# multiple_frequency_divider_1_1.net
KiCad netlist of a schematic drawn in EAGLE
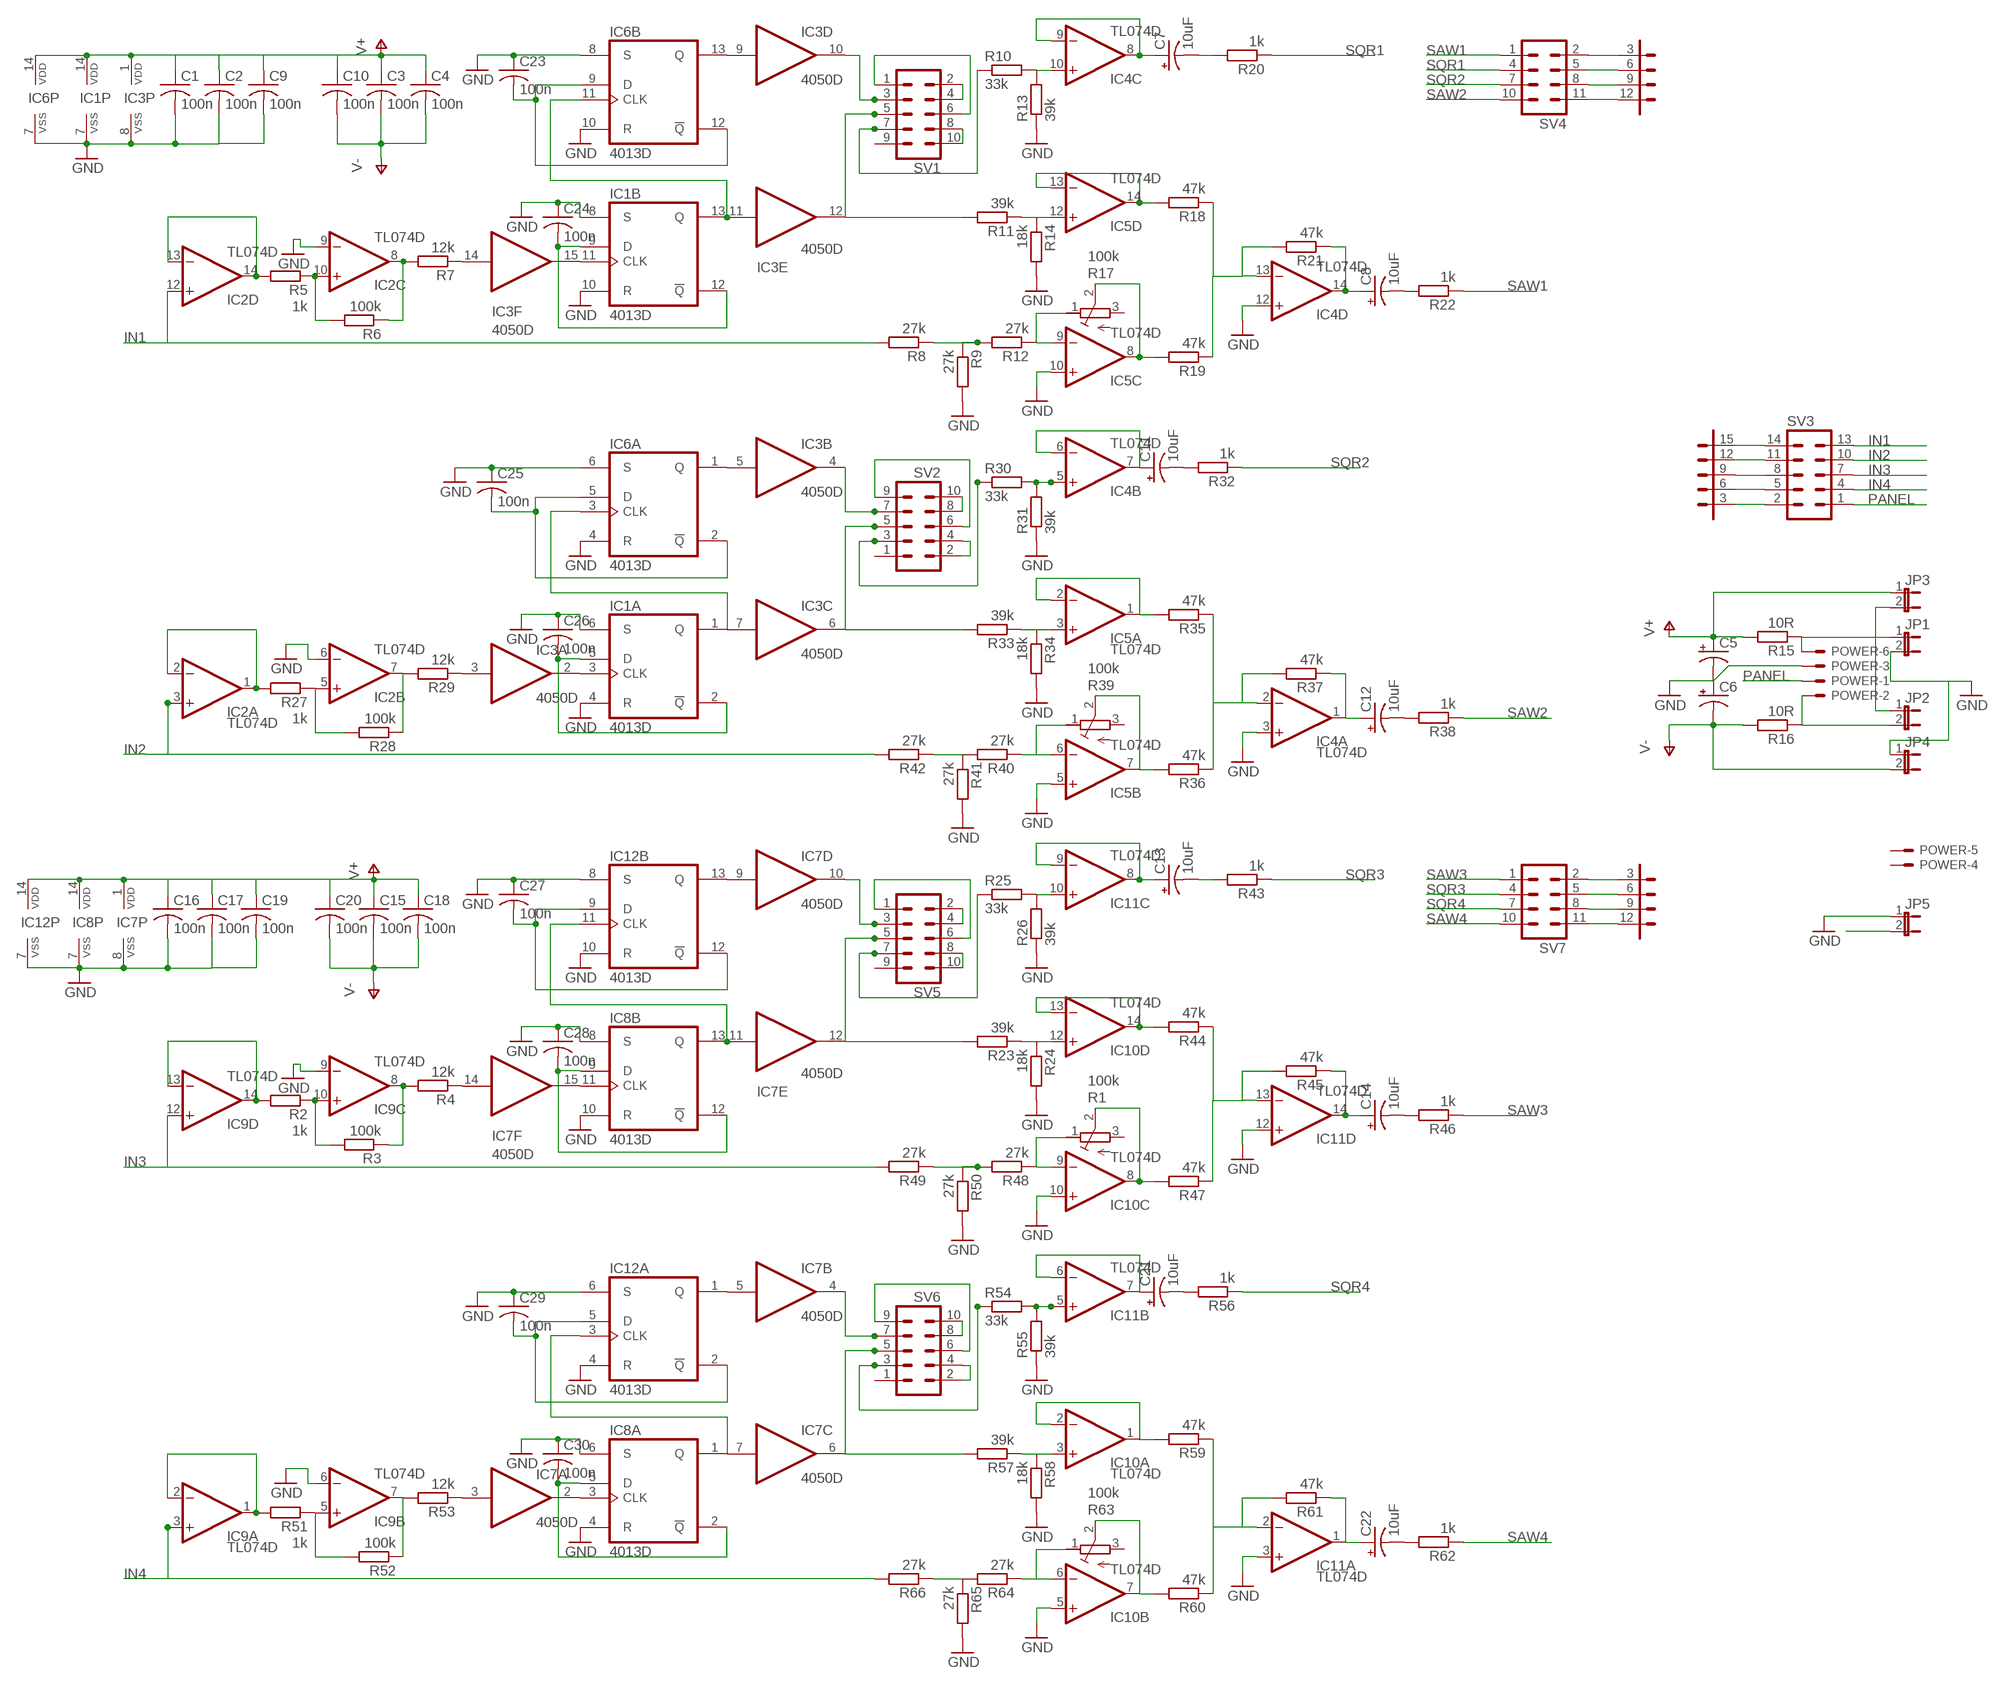
[diagram p0: schematic, sheet 1]

(export (version "E")
  (design (tool "Eeschema 10.0.6"))
  (components
    (comp (ref "C1")
      (value "100n")
      (footprint "eagle-import:C025-024X044")
      (libsource (lib "eagle-import") (part "C-US025-024X044"))
    )
    (comp (ref "C2")
      (value "100n")
      (footprint "eagle-import:C025-024X044")
      (libsource (lib "eagle-import") (part "C-US025-024X044"))
    )
    (comp (ref "C3")
      (value "100n")
      (footprint "eagle-import:C025-024X044")
      (libsource (lib "eagle-import") (part "C-US025-024X044"))
    )
    (comp (ref "C4")
      (value "100n")
      (footprint "eagle-import:C025-024X044")
      (libsource (lib "eagle-import") (part "C-US025-024X044"))
    )
    (comp (ref "C5")
      (value "CPOL-USE2.5-5")
      (footprint "eagle-import:E2,5-5")
      (libsource (lib "eagle-import") (part "CPOL-USE2.5-5"))
    )
    (comp (ref "C6")
      (value "CPOL-USE2.5-5")
      (footprint "eagle-import:E2,5-5")
      (libsource (lib "eagle-import") (part "CPOL-USE2.5-5"))
    )
    (comp (ref "C7")
      (value "10uF")
      (footprint "eagle-import:E2,5-5")
      (libsource (lib "eagle-import") (part "CPOL-USE2.5-5"))
    )
    (comp (ref "C8")
      (value "10uF")
      (footprint "eagle-import:E2,5-5")
      (libsource (lib "eagle-import") (part "CPOL-USE2.5-5"))
    )
    (comp (ref "C9")
      (value "100n")
      (footprint "eagle-import:C025-024X044")
      (libsource (lib "eagle-import") (part "C-US025-024X044"))
    )
    (comp (ref "C10")
      (value "100n")
      (footprint "eagle-import:C025-024X044")
      (libsource (lib "eagle-import") (part "C-US025-024X044"))
    )
    (comp (ref "C11")
      (value "10uF")
      (footprint "eagle-import:E2,5-5")
      (libsource (lib "eagle-import") (part "CPOL-USE2.5-5"))
    )
    (comp (ref "C12")
      (value "10uF")
      (footprint "eagle-import:E2,5-5")
      (libsource (lib "eagle-import") (part "CPOL-USE2.5-5"))
    )
    (comp (ref "C13")
      (value "10uF")
      (footprint "eagle-import:E2,5-5")
      (libsource (lib "eagle-import") (part "CPOL-USE2.5-5"))
    )
    (comp (ref "C14")
      (value "10uF")
      (footprint "eagle-import:E2,5-5")
      (libsource (lib "eagle-import") (part "CPOL-USE2.5-5"))
    )
    (comp (ref "C15")
      (value "100n")
      (footprint "eagle-import:C025-024X044")
      (libsource (lib "eagle-import") (part "C-US025-024X044"))
    )
    (comp (ref "C16")
      (value "100n")
      (footprint "eagle-import:C025-024X044")
      (libsource (lib "eagle-import") (part "C-US025-024X044"))
    )
    (comp (ref "C17")
      (value "100n")
      (footprint "eagle-import:C025-024X044")
      (libsource (lib "eagle-import") (part "C-US025-024X044"))
    )
    (comp (ref "C18")
      (value "100n")
      (footprint "eagle-import:C025-024X044")
      (libsource (lib "eagle-import") (part "C-US025-024X044"))
    )
    (comp (ref "C19")
      (value "100n")
      (footprint "eagle-import:C025-024X044")
      (libsource (lib "eagle-import") (part "C-US025-024X044"))
    )
    (comp (ref "C20")
      (value "100n")
      (footprint "eagle-import:C025-024X044")
      (libsource (lib "eagle-import") (part "C-US025-024X044"))
    )
    (comp (ref "C21")
      (value "10uF")
      (footprint "eagle-import:E2,5-5")
      (libsource (lib "eagle-import") (part "CPOL-USE2.5-5"))
    )
    (comp (ref "C22")
      (value "10uF")
      (footprint "eagle-import:E2,5-5")
      (libsource (lib "eagle-import") (part "CPOL-USE2.5-5"))
    )
    (comp (ref "C23")
      (value "100n")
      (footprint "eagle-import:C025-024X044")
      (libsource (lib "eagle-import") (part "C-US025-024X044"))
    )
    (comp (ref "C24")
      (value "100n")
      (footprint "eagle-import:C025-024X044")
      (libsource (lib "eagle-import") (part "C-US025-024X044"))
    )
    (comp (ref "C25")
      (value "100n")
      (footprint "eagle-import:C025-024X044")
      (libsource (lib "eagle-import") (part "C-US025-024X044"))
    )
    (comp (ref "C26")
      (value "100n")
      (footprint "eagle-import:C025-024X044")
      (libsource (lib "eagle-import") (part "C-US025-024X044"))
    )
    (comp (ref "C27")
      (value "100n")
      (footprint "eagle-import:C025-024X044")
      (libsource (lib "eagle-import") (part "C-US025-024X044"))
    )
    (comp (ref "C28")
      (value "100n")
      (footprint "eagle-import:C025-024X044")
      (libsource (lib "eagle-import") (part "C-US025-024X044"))
    )
    (comp (ref "C29")
      (value "100n")
      (footprint "eagle-import:C025-024X044")
      (libsource (lib "eagle-import") (part "C-US025-024X044"))
    )
    (comp (ref "C30")
      (value "100n")
      (footprint "eagle-import:C025-024X044")
      (libsource (lib "eagle-import") (part "C-US025-024X044"))
    )
    (comp (ref "IC1")
      (value "4013D")
      (footprint "eagle-import:SO14")
      (libsource (lib "eagle-import") (part "4013D"))
    )
    (comp (ref "IC2")
      (value "TL074D")
      (footprint "eagle-import:SO14")
      (libsource (lib "eagle-import") (part "TL074D"))
    )
    (comp (ref "IC3")
      (value "4050D")
      (footprint "eagle-import:SO16")
      (libsource (lib "eagle-import") (part "4050D"))
    )
    (comp (ref "IC4")
      (value "TL074D")
      (footprint "eagle-import:SO14")
      (libsource (lib "eagle-import") (part "TL074D"))
    )
    (comp (ref "IC5")
      (value "TL074D")
      (footprint "eagle-import:SO14")
      (libsource (lib "eagle-import") (part "TL074D"))
    )
    (comp (ref "IC6")
      (value "4013D")
      (footprint "eagle-import:SO14")
      (libsource (lib "eagle-import") (part "4013D"))
    )
    (comp (ref "IC7")
      (value "4050D")
      (footprint "eagle-import:SO16")
      (libsource (lib "eagle-import") (part "4050D"))
    )
    (comp (ref "IC8")
      (value "4013D")
      (footprint "eagle-import:SO14")
      (libsource (lib "eagle-import") (part "4013D"))
    )
    (comp (ref "IC9")
      (value "TL074D")
      (footprint "eagle-import:SO14")
      (libsource (lib "eagle-import") (part "TL074D"))
    )
    (comp (ref "IC10")
      (value "TL074D")
      (footprint "eagle-import:SO14")
      (libsource (lib "eagle-import") (part "TL074D"))
    )
    (comp (ref "IC11")
      (value "TL074D")
      (footprint "eagle-import:SO14")
      (libsource (lib "eagle-import") (part "TL074D"))
    )
    (comp (ref "IC12")
      (value "4013D")
      (footprint "eagle-import:SO14")
      (libsource (lib "eagle-import") (part "4013D"))
    )
    (comp (ref "JP1")
      (value "JP1E")
      (footprint "eagle-import:JP1")
      (libsource (lib "eagle-import") (part "JP1E"))
    )
    (comp (ref "JP2")
      (value "JP1E")
      (footprint "eagle-import:JP1")
      (libsource (lib "eagle-import") (part "JP1E"))
    )
    (comp (ref "JP3")
      (value "JP1E")
      (footprint "eagle-import:JP1")
      (libsource (lib "eagle-import") (part "JP1E"))
    )
    (comp (ref "JP4")
      (value "JP1E")
      (footprint "eagle-import:JP1")
      (libsource (lib "eagle-import") (part "JP1E"))
    )
    (comp (ref "JP5")
      (value "JP1E")
      (footprint "eagle-import:JP1")
      (libsource (lib "eagle-import") (part "JP1E"))
    )
    (comp (ref "POWER")
      (value "22-23-2061")
      (footprint "eagle-import:22-23-2061")
      (fields (field (name "MF") "MOLEX"))
      (libsource (lib "eagle-import") (part "22-23-2061"))
    )
    (comp (ref "R1")
      (value "100k")
      (footprint "eagle-import:RTRIMT93YA")
      (libsource (lib "eagle-import") (part "R-TRIMMT93YA"))
    )
    (comp (ref "R2")
      (value "1k")
      (footprint "eagle-import:0204_5")
      (libsource (lib "eagle-import") (part "R-EU_0204/5"))
    )
    (comp (ref "R3")
      (value "100k")
      (footprint "eagle-import:0204_5")
      (libsource (lib "eagle-import") (part "R-EU_0204/5"))
    )
    (comp (ref "R4")
      (value "12k")
      (footprint "eagle-import:0204_5")
      (libsource (lib "eagle-import") (part "R-EU_0204/5"))
    )
    (comp (ref "R5")
      (value "1k")
      (footprint "eagle-import:0204_5")
      (libsource (lib "eagle-import") (part "R-EU_0204/5"))
    )
    (comp (ref "R6")
      (value "100k")
      (footprint "eagle-import:0204_5")
      (libsource (lib "eagle-import") (part "R-EU_0204/5"))
    )
    (comp (ref "R7")
      (value "12k")
      (footprint "eagle-import:0204_5")
      (libsource (lib "eagle-import") (part "R-EU_0204/5"))
    )
    (comp (ref "R8")
      (value "27k")
      (footprint "eagle-import:0204_5")
      (libsource (lib "eagle-import") (part "R-EU_0204/5"))
    )
    (comp (ref "R9")
      (value "27k")
      (footprint "eagle-import:0204_5")
      (libsource (lib "eagle-import") (part "R-EU_0204/5"))
    )
    (comp (ref "R10")
      (value "33k")
      (footprint "eagle-import:0204_5")
      (libsource (lib "eagle-import") (part "R-EU_0204/5"))
    )
    (comp (ref "R11")
      (value "39k")
      (footprint "eagle-import:0204_5")
      (libsource (lib "eagle-import") (part "R-EU_0204/5"))
    )
    (comp (ref "R12")
      (value "27k")
      (footprint "eagle-import:0204_5")
      (libsource (lib "eagle-import") (part "R-EU_0204/5"))
    )
    (comp (ref "R13")
      (value "39k")
      (footprint "eagle-import:0204_5")
      (libsource (lib "eagle-import") (part "R-EU_0204/5"))
    )
    (comp (ref "R14")
      (value "18k")
      (footprint "eagle-import:0204_5")
      (libsource (lib "eagle-import") (part "R-EU_0204/5"))
    )
    (comp (ref "R15")
      (value "10R")
      (footprint "eagle-import:0207_7")
      (libsource (lib "eagle-import") (part "resistor_R-EU_0207/7"))
    )
    (comp (ref "R16")
      (value "10R")
      (footprint "eagle-import:0207_7")
      (libsource (lib "eagle-import") (part "resistor_R-EU_0207/7"))
    )
    (comp (ref "R17")
      (value "100k")
      (footprint "eagle-import:RTRIMT93YA")
      (libsource (lib "eagle-import") (part "R-TRIMMT93YA"))
    )
    (comp (ref "R18")
      (value "47k")
      (footprint "eagle-import:0204_5")
      (libsource (lib "eagle-import") (part "R-EU_0204/5"))
    )
    (comp (ref "R19")
      (value "47k")
      (footprint "eagle-import:0204_5")
      (libsource (lib "eagle-import") (part "R-EU_0204/5"))
    )
    (comp (ref "R20")
      (value "1k")
      (footprint "eagle-import:0204_5")
      (libsource (lib "eagle-import") (part "R-EU_0204/5"))
    )
    (comp (ref "R21")
      (value "47k")
      (footprint "eagle-import:0204_5")
      (libsource (lib "eagle-import") (part "R-EU_0204/5"))
    )
    (comp (ref "R22")
      (value "1k")
      (footprint "eagle-import:0204_5")
      (libsource (lib "eagle-import") (part "R-EU_0204/5"))
    )
    (comp (ref "R23")
      (value "39k")
      (footprint "eagle-import:0204_5")
      (libsource (lib "eagle-import") (part "R-EU_0204/5"))
    )
    (comp (ref "R24")
      (value "18k")
      (footprint "eagle-import:0204_5")
      (libsource (lib "eagle-import") (part "R-EU_0204/5"))
    )
    (comp (ref "R25")
      (value "33k")
      (footprint "eagle-import:0204_5")
      (libsource (lib "eagle-import") (part "R-EU_0204/5"))
    )
    (comp (ref "R26")
      (value "39k")
      (footprint "eagle-import:0204_5")
      (libsource (lib "eagle-import") (part "R-EU_0204/5"))
    )
    (comp (ref "R27")
      (value "1k")
      (footprint "eagle-import:0204_5")
      (libsource (lib "eagle-import") (part "R-EU_0204/5"))
    )
    (comp (ref "R28")
      (value "100k")
      (footprint "eagle-import:0204_5")
      (libsource (lib "eagle-import") (part "R-EU_0204/5"))
    )
    (comp (ref "R29")
      (value "12k")
      (footprint "eagle-import:0204_5")
      (libsource (lib "eagle-import") (part "R-EU_0204/5"))
    )
    (comp (ref "R30")
      (value "33k")
      (footprint "eagle-import:0204_5")
      (libsource (lib "eagle-import") (part "R-EU_0204/5"))
    )
    (comp (ref "R31")
      (value "39k")
      (footprint "eagle-import:0204_5")
      (libsource (lib "eagle-import") (part "R-EU_0204/5"))
    )
    (comp (ref "R32")
      (value "1k")
      (footprint "eagle-import:0204_5")
      (libsource (lib "eagle-import") (part "R-EU_0204/5"))
    )
    (comp (ref "R33")
      (value "39k")
      (footprint "eagle-import:0204_5")
      (libsource (lib "eagle-import") (part "R-EU_0204/5"))
    )
    (comp (ref "R34")
      (value "18k")
      (footprint "eagle-import:0204_5")
      (libsource (lib "eagle-import") (part "R-EU_0204/5"))
    )
    (comp (ref "R35")
      (value "47k")
      (footprint "eagle-import:0204_5")
      (libsource (lib "eagle-import") (part "R-EU_0204/5"))
    )
    (comp (ref "R36")
      (value "47k")
      (footprint "eagle-import:0204_5")
      (libsource (lib "eagle-import") (part "R-EU_0204/5"))
    )
    (comp (ref "R37")
      (value "47k")
      (footprint "eagle-import:0204_5")
      (libsource (lib "eagle-import") (part "R-EU_0204/5"))
    )
    (comp (ref "R38")
      (value "1k")
      (footprint "eagle-import:0204_5")
      (libsource (lib "eagle-import") (part "R-EU_0204/5"))
    )
    (comp (ref "R39")
      (value "100k")
      (footprint "eagle-import:RTRIMT93YA")
      (libsource (lib "eagle-import") (part "R-TRIMMT93YA"))
    )
    (comp (ref "R40")
      (value "27k")
      (footprint "eagle-import:0204_5")
      (libsource (lib "eagle-import") (part "R-EU_0204/5"))
    )
    (comp (ref "R41")
      (value "27k")
      (footprint "eagle-import:0204_5")
      (libsource (lib "eagle-import") (part "R-EU_0204/5"))
    )
    (comp (ref "R42")
      (value "27k")
      (footprint "eagle-import:0204_5")
      (libsource (lib "eagle-import") (part "R-EU_0204/5"))
    )
    (comp (ref "R43")
      (value "1k")
      (footprint "eagle-import:0204_5")
      (libsource (lib "eagle-import") (part "R-EU_0204/5"))
    )
    (comp (ref "R44")
      (value "47k")
      (footprint "eagle-import:0204_5")
      (libsource (lib "eagle-import") (part "R-EU_0204/5"))
    )
    (comp (ref "R45")
      (value "47k")
      (footprint "eagle-import:0204_5")
      (libsource (lib "eagle-import") (part "R-EU_0204/5"))
    )
    (comp (ref "R46")
      (value "1k")
      (footprint "eagle-import:0204_5")
      (libsource (lib "eagle-import") (part "R-EU_0204/5"))
    )
    (comp (ref "R47")
      (value "47k")
      (footprint "eagle-import:0204_5")
      (libsource (lib "eagle-import") (part "R-EU_0204/5"))
    )
    (comp (ref "R48")
      (value "27k")
      (footprint "eagle-import:0204_5")
      (libsource (lib "eagle-import") (part "R-EU_0204/5"))
    )
    (comp (ref "R49")
      (value "27k")
      (footprint "eagle-import:0204_5")
      (libsource (lib "eagle-import") (part "R-EU_0204/5"))
    )
    (comp (ref "R50")
      (value "27k")
      (footprint "eagle-import:0204_5")
      (libsource (lib "eagle-import") (part "R-EU_0204/5"))
    )
    (comp (ref "R51")
      (value "1k")
      (footprint "eagle-import:0204_5")
      (libsource (lib "eagle-import") (part "R-EU_0204/5"))
    )
    (comp (ref "R52")
      (value "100k")
      (footprint "eagle-import:0204_5")
      (libsource (lib "eagle-import") (part "R-EU_0204/5"))
    )
    (comp (ref "R53")
      (value "12k")
      (footprint "eagle-import:0204_5")
      (libsource (lib "eagle-import") (part "R-EU_0204/5"))
    )
    (comp (ref "R54")
      (value "33k")
      (footprint "eagle-import:0204_5")
      (libsource (lib "eagle-import") (part "R-EU_0204/5"))
    )
    (comp (ref "R55")
      (value "39k")
      (footprint "eagle-import:0204_5")
      (libsource (lib "eagle-import") (part "R-EU_0204/5"))
    )
    (comp (ref "R56")
      (value "1k")
      (footprint "eagle-import:0204_5")
      (libsource (lib "eagle-import") (part "R-EU_0204/5"))
    )
    (comp (ref "R57")
      (value "39k")
      (footprint "eagle-import:0204_5")
      (libsource (lib "eagle-import") (part "R-EU_0204/5"))
    )
    (comp (ref "R58")
      (value "18k")
      (footprint "eagle-import:0204_5")
      (libsource (lib "eagle-import") (part "R-EU_0204/5"))
    )
    (comp (ref "R59")
      (value "47k")
      (footprint "eagle-import:0204_5")
      (libsource (lib "eagle-import") (part "R-EU_0204/5"))
    )
    (comp (ref "R60")
      (value "47k")
      (footprint "eagle-import:0204_5")
      (libsource (lib "eagle-import") (part "R-EU_0204/5"))
    )
    (comp (ref "R61")
      (value "47k")
      (footprint "eagle-import:0204_5")
      (libsource (lib "eagle-import") (part "R-EU_0204/5"))
    )
    (comp (ref "R62")
      (value "1k")
      (footprint "eagle-import:0204_5")
      (libsource (lib "eagle-import") (part "R-EU_0204/5"))
    )
    (comp (ref "R63")
      (value "100k")
      (footprint "eagle-import:RTRIMT93YA")
      (libsource (lib "eagle-import") (part "R-TRIMMT93YA"))
    )
    (comp (ref "R64")
      (value "27k")
      (footprint "eagle-import:0204_5")
      (libsource (lib "eagle-import") (part "R-EU_0204/5"))
    )
    (comp (ref "R65")
      (value "27k")
      (footprint "eagle-import:0204_5")
      (libsource (lib "eagle-import") (part "R-EU_0204/5"))
    )
    (comp (ref "R66")
      (value "27k")
      (footprint "eagle-import:0204_5")
      (libsource (lib "eagle-import") (part "R-EU_0204/5"))
    )
    (comp (ref "SV1")
      (value "MA05-2")
      (footprint "eagle-import:MA05-2")
      (libsource (lib "eagle-import") (part "MA05-2"))
    )
    (comp (ref "SV2")
      (value "MA05-2")
      (footprint "eagle-import:MA05-2")
      (libsource (lib "eagle-import") (part "MA05-2"))
    )
    (comp (ref "SV3")
      (value "MA05-3")
      (footprint "eagle-import:MA05-3")
      (libsource (lib "eagle-import") (part "MA05-3"))
    )
    (comp (ref "SV4")
      (value "MA04-3")
      (footprint "eagle-import:MA04-3")
      (libsource (lib "eagle-import") (part "MA04-3"))
    )
    (comp (ref "SV5")
      (value "MA05-2")
      (footprint "eagle-import:MA05-2")
      (libsource (lib "eagle-import") (part "MA05-2"))
    )
    (comp (ref "SV6")
      (value "MA05-2")
      (footprint "eagle-import:MA05-2")
      (libsource (lib "eagle-import") (part "MA05-2"))
    )
    (comp (ref "SV7")
      (value "MA04-3")
      (footprint "eagle-import:MA04-3")
      (libsource (lib "eagle-import") (part "MA04-3"))
    )
  )
  (nets
    (net (code "1") (name "/IN1") (class "Default")
      (node (ref "IC2") (pin "12") (pinfunction "+IN_12") (pintype "input"))
      (node (ref "R8") (pin "2") (pinfunction "2_2") (pintype "passive"))
      (node (ref "SV3") (pin "13") (pinfunction "13_13") (pintype "passive"))
    )
    (net (code "2") (name "/IN2") (class "Default")
      (node (ref "IC2") (pin "3") (pinfunction "+IN_3") (pintype "input"))
      (node (ref "R42") (pin "2") (pinfunction "2_2") (pintype "passive"))
      (node (ref "SV3") (pin "10") (pinfunction "10_10") (pintype "passive"))
    )
    (net (code "3") (name "/IN3") (class "Default")
      (node (ref "IC9") (pin "12") (pinfunction "+IN_12") (pintype "input"))
      (node (ref "R49") (pin "2") (pinfunction "2_2") (pintype "passive"))
      (node (ref "SV3") (pin "7") (pinfunction "7_7") (pintype "passive"))
    )
    (net (code "4") (name "/IN4") (class "Default")
      (node (ref "IC9") (pin "3") (pinfunction "+IN_3") (pintype "input"))
      (node (ref "R66") (pin "2") (pinfunction "2_2") (pintype "passive"))
      (node (ref "SV3") (pin "4") (pinfunction "4_4") (pintype "passive"))
    )
    (net (code "5") (name "/PANEL") (class "Default")
      (node (ref "JP2") (pin "1") (pinfunction "1_1") (pintype "passive"))
      (node (ref "JP3") (pin "2") (pinfunction "2_2") (pintype "passive"))
      (node (ref "JP5") (pin "2") (pinfunction "2_2") (pintype "passive"))
      (node (ref "POWER") (pin "1") (pinfunction "S_1") (pintype "passive"))
      (node (ref "SV3") (pin "1") (pinfunction "1_1") (pintype "passive"))
    )
    (net (code "6") (name "/SAW1") (class "Default")
      (node (ref "R22") (pin "1") (pinfunction "1_1") (pintype "passive"))
      (node (ref "SV4") (pin "1") (pinfunction "1_1") (pintype "passive"))
    )
    (net (code "7") (name "/SAW2") (class "Default")
      (node (ref "R38") (pin "1") (pinfunction "1_1") (pintype "passive"))
      (node (ref "SV4") (pin "10") (pinfunction "10_10") (pintype "passive"))
    )
    (net (code "8") (name "/SAW3") (class "Default")
      (node (ref "R46") (pin "1") (pinfunction "1_1") (pintype "passive"))
      (node (ref "SV7") (pin "1") (pinfunction "1_1") (pintype "passive"))
    )
    (net (code "9") (name "/SAW4") (class "Default")
      (node (ref "R62") (pin "1") (pinfunction "1_1") (pintype "passive"))
      (node (ref "SV7") (pin "10") (pinfunction "10_10") (pintype "passive"))
    )
    (net (code "10") (name "/SQR1") (class "Default")
      (node (ref "R20") (pin "1") (pinfunction "1_1") (pintype "passive"))
      (node (ref "SV4") (pin "4") (pinfunction "4_4") (pintype "passive"))
    )
    (net (code "11") (name "/SQR2") (class "Default")
      (node (ref "R32") (pin "1") (pinfunction "1_1") (pintype "passive"))
      (node (ref "SV4") (pin "7") (pinfunction "7_7") (pintype "passive"))
    )
    (net (code "12") (name "/SQR3") (class "Default")
      (node (ref "R43") (pin "1") (pinfunction "1_1") (pintype "passive"))
      (node (ref "SV7") (pin "4") (pinfunction "4_4") (pintype "passive"))
    )
    (net (code "13") (name "/SQR4") (class "Default")
      (node (ref "R56") (pin "1") (pinfunction "1_1") (pintype "passive"))
      (node (ref "SV7") (pin "7") (pinfunction "7_7") (pintype "passive"))
    )
    (net (code "14") (name "GND") (class "Default")
      (node (ref "C1") (pin "2") (pinfunction "2_2") (pintype "passive"))
      (node (ref "C16") (pin "2") (pinfunction "2_2") (pintype "passive"))
      (node (ref "C17") (pin "2") (pinfunction "2_2") (pintype "passive"))
      (node (ref "C19") (pin "2") (pinfunction "2_2") (pintype "passive"))
      (node (ref "C2") (pin "2") (pinfunction "2_2") (pintype "passive"))
      (node (ref "C23") (pin "1") (pinfunction "1_1") (pintype "passive"))
      (node (ref "C24") (pin "1") (pinfunction "1_1") (pintype "passive"))
      (node (ref "C25") (pin "1") (pinfunction "1_1") (pintype "passive"))
      (node (ref "C26") (pin "1") (pinfunction "1_1") (pintype "passive"))
      (node (ref "C27") (pin "1") (pinfunction "1_1") (pintype "passive"))
      (node (ref "C28") (pin "1") (pinfunction "1_1") (pintype "passive"))
      (node (ref "C29") (pin "1") (pinfunction "1_1") (pintype "passive"))
      (node (ref "C30") (pin "1") (pinfunction "1_1") (pintype "passive"))
      (node (ref "C5") (pin "-") (pinfunction "-_-") (pintype "passive"))
      (node (ref "C6") (pin "+") (pinfunction "+_+") (pintype "passive"))
      (node (ref "C9") (pin "2") (pinfunction "2_2") (pintype "passive"))
      (node (ref "IC1") (pin "10") (pinfunction "R_10") (pintype "input"))
      (node (ref "IC1") (pin "4") (pinfunction "R_4") (pintype "input"))
      (node (ref "IC1") (pin "6") (pinfunction "S_6") (pintype "input"))
      (node (ref "IC1") (pin "7") (pinfunction "VSS_7") (pintype "power_in"))
      (node (ref "IC1") (pin "8") (pinfunction "S_8") (pintype "input"))
      (node (ref "IC10") (pin "10") (pinfunction "+IN_10") (pintype "input"))
      (node (ref "IC10") (pin "5") (pinfunction "+IN_5") (pintype "input"))
      (node (ref "IC11") (pin "12") (pinfunction "+IN_12") (pintype "input"))
      (node (ref "IC11") (pin "3") (pinfunction "+IN_3") (pintype "input"))
      (node (ref "IC12") (pin "10") (pinfunction "R_10") (pintype "input"))
      (node (ref "IC12") (pin "4") (pinfunction "R_4") (pintype "input"))
      (node (ref "IC12") (pin "6") (pinfunction "S_6") (pintype "input"))
      (node (ref "IC12") (pin "7") (pinfunction "VSS_7") (pintype "power_in"))
      (node (ref "IC12") (pin "8") (pinfunction "S_8") (pintype "input"))
      (node (ref "IC2") (pin "6") (pinfunction "-IN_6") (pintype "input"))
      (node (ref "IC2") (pin "9") (pinfunction "-IN_9") (pintype "input"))
      (node (ref "IC3") (pin "8") (pinfunction "VSS_8") (pintype "power_in"))
      (node (ref "IC4") (pin "12") (pinfunction "+IN_12") (pintype "input"))
      (node (ref "IC4") (pin "3") (pinfunction "+IN_3") (pintype "input"))
      (node (ref "IC5") (pin "10") (pinfunction "+IN_10") (pintype "input"))
      (node (ref "IC5") (pin "5") (pinfunction "+IN_5") (pintype "input"))
      (node (ref "IC6") (pin "10") (pinfunction "R_10") (pintype "input"))
      (node (ref "IC6") (pin "4") (pinfunction "R_4") (pintype "input"))
      (node (ref "IC6") (pin "6") (pinfunction "S_6") (pintype "input"))
      (node (ref "IC6") (pin "7") (pinfunction "VSS_7") (pintype "power_in"))
      (node (ref "IC6") (pin "8") (pinfunction "S_8") (pintype "input"))
      (node (ref "IC7") (pin "8") (pinfunction "VSS_8") (pintype "power_in"))
      (node (ref "IC8") (pin "10") (pinfunction "R_10") (pintype "input"))
      (node (ref "IC8") (pin "4") (pinfunction "R_4") (pintype "input"))
      (node (ref "IC8") (pin "6") (pinfunction "S_6") (pintype "input"))
      (node (ref "IC8") (pin "7") (pinfunction "VSS_7") (pintype "power_in"))
      (node (ref "IC8") (pin "8") (pinfunction "S_8") (pintype "input"))
      (node (ref "IC9") (pin "6") (pinfunction "-IN_6") (pintype "input"))
      (node (ref "IC9") (pin "9") (pinfunction "-IN_9") (pintype "input"))
      (node (ref "JP1") (pin "2") (pinfunction "2_2") (pintype "passive"))
      (node (ref "JP4") (pin "1") (pinfunction "1_1") (pintype "passive"))
      (node (ref "JP5") (pin "1") (pinfunction "1_1") (pintype "passive"))
      (node (ref "POWER") (pin "3") (pinfunction "S_3") (pintype "passive"))
      (node (ref "R13") (pin "1") (pinfunction "1_1") (pintype "passive"))
      (node (ref "R14") (pin "2") (pinfunction "2_2") (pintype "passive"))
      (node (ref "R24") (pin "2") (pinfunction "2_2") (pintype "passive"))
      (node (ref "R26") (pin "1") (pinfunction "1_1") (pintype "passive"))
      (node (ref "R31") (pin "1") (pinfunction "1_1") (pintype "passive"))
      (node (ref "R34") (pin "2") (pinfunction "2_2") (pintype "passive"))
      (node (ref "R41") (pin "2") (pinfunction "2_2") (pintype "passive"))
      (node (ref "R50") (pin "2") (pinfunction "2_2") (pintype "passive"))
      (node (ref "R55") (pin "1") (pinfunction "1_1") (pintype "passive"))
      (node (ref "R58") (pin "2") (pinfunction "2_2") (pintype "passive"))
      (node (ref "R65") (pin "2") (pinfunction "2_2") (pintype "passive"))
      (node (ref "R9") (pin "2") (pinfunction "2_2") (pintype "passive"))
    )
    (net (code "15") (name "Net-(C7-Pad-)") (class "Default")
      (node (ref "C7") (pin "-") (pinfunction "-_-") (pintype "passive"))
      (node (ref "R20") (pin "2") (pinfunction "2_2") (pintype "passive"))
    )
    (net (code "16") (name "Net-(C8-Pad-)") (class "Default")
      (node (ref "C8") (pin "-") (pinfunction "-_-") (pintype "passive"))
      (node (ref "R22") (pin "2") (pinfunction "2_2") (pintype "passive"))
    )
    (net (code "17") (name "Net-(C11-Pad-)") (class "Default")
      (node (ref "C11") (pin "-") (pinfunction "-_-") (pintype "passive"))
      (node (ref "R32") (pin "2") (pinfunction "2_2") (pintype "passive"))
    )
    (net (code "18") (name "Net-(C12-Pad-)") (class "Default")
      (node (ref "C12") (pin "-") (pinfunction "-_-") (pintype "passive"))
      (node (ref "R38") (pin "2") (pinfunction "2_2") (pintype "passive"))
    )
    (net (code "19") (name "Net-(C13-Pad-)") (class "Default")
      (node (ref "C13") (pin "-") (pinfunction "-_-") (pintype "passive"))
      (node (ref "R43") (pin "2") (pinfunction "2_2") (pintype "passive"))
    )
    (net (code "20") (name "Net-(C14-Pad-)") (class "Default")
      (node (ref "C14") (pin "-") (pinfunction "-_-") (pintype "passive"))
      (node (ref "R46") (pin "2") (pinfunction "2_2") (pintype "passive"))
    )
    (net (code "21") (name "Net-(C21-Pad-)") (class "Default")
      (node (ref "C21") (pin "-") (pinfunction "-_-") (pintype "passive"))
      (node (ref "R56") (pin "2") (pinfunction "2_2") (pintype "passive"))
    )
    (net (code "22") (name "Net-(C22-Pad-)") (class "Default")
      (node (ref "C22") (pin "-") (pinfunction "-_-") (pintype "passive"))
      (node (ref "R62") (pin "2") (pinfunction "2_2") (pintype "passive"))
    )
    (net (code "23") (name "Net-(IC1A-CLK)") (class "Default")
      (node (ref "IC1") (pin "3") (pinfunction "CLK_3") (pintype "input"))
      (node (ref "IC3") (pin "2") (pinfunction "O_2") (pintype "output"))
    )
    (net (code "24") (name "Net-(IC1A-D)") (class "Default")
      (node (ref "C26") (pin "2") (pinfunction "2_2") (pintype "passive"))
      (node (ref "IC1") (pin "2") (pinfunction "~{Q}_2") (pintype "output"))
      (node (ref "IC1") (pin "5") (pinfunction "D_5") (pintype "input"))
    )
    (net (code "25") (name "Net-(IC1A-Q)") (class "Default")
      (node (ref "IC1") (pin "1") (pinfunction "Q_1") (pintype "output"))
      (node (ref "IC3") (pin "7") (pinfunction "I_7") (pintype "input"))
      (node (ref "IC6") (pin "3") (pinfunction "CLK_3") (pintype "input"))
    )
    (net (code "26") (name "Net-(IC1B-CLK)") (class "Default")
      (node (ref "IC1") (pin "11") (pinfunction "CLK_11") (pintype "input"))
      (node (ref "IC3") (pin "15") (pinfunction "O_15") (pintype "output"))
    )
    (net (code "27") (name "Net-(IC1B-D)") (class "Default")
      (node (ref "C24") (pin "2") (pinfunction "2_2") (pintype "passive"))
      (node (ref "IC1") (pin "12") (pinfunction "~{Q}_12") (pintype "output"))
      (node (ref "IC1") (pin "9") (pinfunction "D_9") (pintype "input"))
    )
    (net (code "28") (name "Net-(IC1B-Q)") (class "Default")
      (node (ref "IC1") (pin "13") (pinfunction "Q_13") (pintype "output"))
      (node (ref "IC3") (pin "11") (pinfunction "I_11") (pintype "input"))
      (node (ref "IC6") (pin "11") (pinfunction "CLK_11") (pintype "input"))
    )
    (net (code "29") (name "Net-(IC2A--IN)") (class "Default")
      (node (ref "IC2") (pin "1") (pinfunction "OUT_1") (pintype "output"))
      (node (ref "IC2") (pin "2") (pinfunction "-IN_2") (pintype "input"))
      (node (ref "R27") (pin "2") (pinfunction "2_2") (pintype "passive"))
    )
    (net (code "30") (name "Net-(IC2B-+IN)") (class "Default")
      (node (ref "IC2") (pin "5") (pinfunction "+IN_5") (pintype "input"))
      (node (ref "R27") (pin "1") (pinfunction "1_1") (pintype "passive"))
      (node (ref "R28") (pin "2") (pinfunction "2_2") (pintype "passive"))
    )
    (net (code "31") (name "Net-(IC2B-OUT)") (class "Default")
      (node (ref "IC2") (pin "7") (pinfunction "OUT_7") (pintype "output"))
      (node (ref "R28") (pin "1") (pinfunction "1_1") (pintype "passive"))
      (node (ref "R29") (pin "2") (pinfunction "2_2") (pintype "passive"))
    )
    (net (code "32") (name "Net-(IC2C-+IN)") (class "Default")
      (node (ref "IC2") (pin "10") (pinfunction "+IN_10") (pintype "input"))
      (node (ref "R5") (pin "1") (pinfunction "1_1") (pintype "passive"))
      (node (ref "R6") (pin "2") (pinfunction "2_2") (pintype "passive"))
    )
    (net (code "33") (name "Net-(IC2C-OUT)") (class "Default")
      (node (ref "IC2") (pin "8") (pinfunction "OUT_8") (pintype "output"))
      (node (ref "R6") (pin "1") (pinfunction "1_1") (pintype "passive"))
      (node (ref "R7") (pin "2") (pinfunction "2_2") (pintype "passive"))
    )
    (net (code "34") (name "Net-(IC2D--IN)") (class "Default")
      (node (ref "IC2") (pin "13") (pinfunction "-IN_13") (pintype "input"))
      (node (ref "IC2") (pin "14") (pinfunction "OUT_14") (pintype "output"))
      (node (ref "R5") (pin "2") (pinfunction "2_2") (pintype "passive"))
    )
    (net (code "35") (name "Net-(IC3A-I)") (class "Default")
      (node (ref "IC3") (pin "3") (pinfunction "I_3") (pintype "input"))
      (node (ref "R29") (pin "1") (pinfunction "1_1") (pintype "passive"))
    )
    (net (code "36") (name "Net-(IC3B-I)") (class "Default")
      (node (ref "IC3") (pin "5") (pinfunction "I_5") (pintype "input"))
      (node (ref "IC6") (pin "1") (pinfunction "Q_1") (pintype "output"))
    )
    (net (code "37") (name "Net-(IC3B-O)") (class "Default")
      (node (ref "IC3") (pin "4") (pinfunction "O_4") (pintype "output"))
      (node (ref "SV2") (pin "7") (pinfunction "7_7") (pintype "passive"))
    )
    (net (code "38") (name "Net-(IC3C-O)") (class "Default")
      (node (ref "IC3") (pin "6") (pinfunction "O_6") (pintype "output"))
      (node (ref "R33") (pin "2") (pinfunction "2_2") (pintype "passive"))
      (node (ref "SV2") (pin "5") (pinfunction "5_5") (pintype "passive"))
    )
    (net (code "39") (name "Net-(IC3D-I)") (class "Default")
      (node (ref "IC3") (pin "9") (pinfunction "I_9") (pintype "input"))
      (node (ref "IC6") (pin "13") (pinfunction "Q_13") (pintype "output"))
    )
    (net (code "40") (name "Net-(IC3D-O)") (class "Default")
      (node (ref "IC3") (pin "10") (pinfunction "O_10") (pintype "output"))
      (node (ref "SV1") (pin "3") (pinfunction "3_3") (pintype "passive"))
    )
    (net (code "41") (name "Net-(IC3E-O)") (class "Default")
      (node (ref "IC3") (pin "12") (pinfunction "O_12") (pintype "output"))
      (node (ref "R11") (pin "2") (pinfunction "2_2") (pintype "passive"))
      (node (ref "SV1") (pin "5") (pinfunction "5_5") (pintype "passive"))
    )
    (net (code "42") (name "Net-(IC3F-I)") (class "Default")
      (node (ref "IC3") (pin "14") (pinfunction "I_14") (pintype "input"))
      (node (ref "R7") (pin "1") (pinfunction "1_1") (pintype "passive"))
    )
    (net (code "43") (name "Net-(IC4A--IN)") (class "Default")
      (node (ref "IC4") (pin "2") (pinfunction "-IN_2") (pintype "input"))
      (node (ref "R35") (pin "1") (pinfunction "1_1") (pintype "passive"))
      (node (ref "R36") (pin "1") (pinfunction "1_1") (pintype "passive"))
      (node (ref "R37") (pin "2") (pinfunction "2_2") (pintype "passive"))
    )
    (net (code "44") (name "Net-(IC4A-OUT)") (class "Default")
      (node (ref "C12") (pin "+") (pinfunction "+_+") (pintype "passive"))
      (node (ref "IC4") (pin "1") (pinfunction "OUT_1") (pintype "output"))
      (node (ref "R37") (pin "1") (pinfunction "1_1") (pintype "passive"))
    )
    (net (code "45") (name "Net-(IC4B-+IN)") (class "Default")
      (node (ref "IC4") (pin "5") (pinfunction "+IN_5") (pintype "input"))
      (node (ref "R30") (pin "2") (pinfunction "2_2") (pintype "passive"))
      (node (ref "R31") (pin "2") (pinfunction "2_2") (pintype "passive"))
    )
    (net (code "46") (name "Net-(IC4B--IN)") (class "Default")
      (node (ref "C11") (pin "+") (pinfunction "+_+") (pintype "passive"))
      (node (ref "IC4") (pin "6") (pinfunction "-IN_6") (pintype "input"))
      (node (ref "IC4") (pin "7") (pinfunction "OUT_7") (pintype "output"))
    )
    (net (code "47") (name "Net-(IC4C-+IN)") (class "Default")
      (node (ref "IC4") (pin "10") (pinfunction "+IN_10") (pintype "input"))
      (node (ref "R10") (pin "2") (pinfunction "2_2") (pintype "passive"))
      (node (ref "R13") (pin "2") (pinfunction "2_2") (pintype "passive"))
    )
    (net (code "48") (name "Net-(IC4C--IN)") (class "Default")
      (node (ref "C7") (pin "+") (pinfunction "+_+") (pintype "passive"))
      (node (ref "IC4") (pin "8") (pinfunction "OUT_8") (pintype "output"))
      (node (ref "IC4") (pin "9") (pinfunction "-IN_9") (pintype "input"))
    )
    (net (code "49") (name "Net-(IC4D--IN)") (class "Default")
      (node (ref "IC4") (pin "13") (pinfunction "-IN_13") (pintype "input"))
      (node (ref "R18") (pin "1") (pinfunction "1_1") (pintype "passive"))
      (node (ref "R19") (pin "1") (pinfunction "1_1") (pintype "passive"))
      (node (ref "R21") (pin "2") (pinfunction "2_2") (pintype "passive"))
    )
    (net (code "50") (name "Net-(IC4D-OUT)") (class "Default")
      (node (ref "C8") (pin "+") (pinfunction "+_+") (pintype "passive"))
      (node (ref "IC4") (pin "14") (pinfunction "OUT_14") (pintype "output"))
      (node (ref "R21") (pin "1") (pinfunction "1_1") (pintype "passive"))
    )
    (net (code "51") (name "Net-(IC5A-+IN)") (class "Default")
      (node (ref "IC5") (pin "3") (pinfunction "+IN_3") (pintype "input"))
      (node (ref "R33") (pin "1") (pinfunction "1_1") (pintype "passive"))
      (node (ref "R34") (pin "1") (pinfunction "1_1") (pintype "passive"))
    )
    (net (code "52") (name "Net-(IC5A--IN)") (class "Default")
      (node (ref "IC5") (pin "1") (pinfunction "OUT_1") (pintype "output"))
      (node (ref "IC5") (pin "2") (pinfunction "-IN_2") (pintype "input"))
      (node (ref "R35") (pin "2") (pinfunction "2_2") (pintype "passive"))
    )
    (net (code "53") (name "Net-(IC5B--IN)") (class "Default")
      (node (ref "IC5") (pin "6") (pinfunction "-IN_6") (pintype "input"))
      (node (ref "R39") (pin "1") (pinfunction "A_1") (pintype "passive"))
      (node (ref "R40") (pin "1") (pinfunction "1_1") (pintype "passive"))
    )
    (net (code "54") (name "Net-(IC5B-OUT)") (class "Default")
      (node (ref "IC5") (pin "7") (pinfunction "OUT_7") (pintype "output"))
      (node (ref "R36") (pin "2") (pinfunction "2_2") (pintype "passive"))
      (node (ref "R39") (pin "2") (pinfunction "S_2") (pintype "passive"))
    )
    (net (code "55") (name "Net-(IC5C--IN)") (class "Default")
      (node (ref "IC5") (pin "9") (pinfunction "-IN_9") (pintype "input"))
      (node (ref "R12") (pin "1") (pinfunction "1_1") (pintype "passive"))
      (node (ref "R17") (pin "1") (pinfunction "A_1") (pintype "passive"))
    )
    (net (code "56") (name "Net-(IC5C-OUT)") (class "Default")
      (node (ref "IC5") (pin "8") (pinfunction "OUT_8") (pintype "output"))
      (node (ref "R17") (pin "2") (pinfunction "S_2") (pintype "passive"))
      (node (ref "R19") (pin "2") (pinfunction "2_2") (pintype "passive"))
    )
    (net (code "57") (name "Net-(IC5D-+IN)") (class "Default")
      (node (ref "IC5") (pin "12") (pinfunction "+IN_12") (pintype "input"))
      (node (ref "R11") (pin "1") (pinfunction "1_1") (pintype "passive"))
      (node (ref "R14") (pin "1") (pinfunction "1_1") (pintype "passive"))
    )
    (net (code "58") (name "Net-(IC5D--IN)") (class "Default")
      (node (ref "IC5") (pin "13") (pinfunction "-IN_13") (pintype "input"))
      (node (ref "IC5") (pin "14") (pinfunction "OUT_14") (pintype "output"))
      (node (ref "R18") (pin "2") (pinfunction "2_2") (pintype "passive"))
    )
    (net (code "59") (name "Net-(IC6A-D)") (class "Default")
      (node (ref "C25") (pin "2") (pinfunction "2_2") (pintype "passive"))
      (node (ref "IC6") (pin "2") (pinfunction "~{Q}_2") (pintype "output"))
      (node (ref "IC6") (pin "5") (pinfunction "D_5") (pintype "input"))
    )
    (net (code "60") (name "Net-(IC6B-D)") (class "Default")
      (node (ref "C23") (pin "2") (pinfunction "2_2") (pintype "passive"))
      (node (ref "IC6") (pin "12") (pinfunction "~{Q}_12") (pintype "output"))
      (node (ref "IC6") (pin "9") (pinfunction "D_9") (pintype "input"))
    )
    (net (code "61") (name "Net-(IC7A-I)") (class "Default")
      (node (ref "IC7") (pin "3") (pinfunction "I_3") (pintype "input"))
      (node (ref "R53") (pin "1") (pinfunction "1_1") (pintype "passive"))
    )
    (net (code "62") (name "Net-(IC7A-O)") (class "Default")
      (node (ref "IC7") (pin "2") (pinfunction "O_2") (pintype "output"))
      (node (ref "IC8") (pin "3") (pinfunction "CLK_3") (pintype "input"))
    )
    (net (code "63") (name "Net-(IC7B-O)") (class "Default")
      (node (ref "IC7") (pin "4") (pinfunction "O_4") (pintype "output"))
      (node (ref "SV6") (pin "7") (pinfunction "7_7") (pintype "passive"))
    )
    (net (code "64") (name "Net-(IC7C-O)") (class "Default")
      (node (ref "IC7") (pin "6") (pinfunction "O_6") (pintype "output"))
      (node (ref "R57") (pin "2") (pinfunction "2_2") (pintype "passive"))
      (node (ref "SV6") (pin "5") (pinfunction "5_5") (pintype "passive"))
    )
    (net (code "65") (name "Net-(IC7D-O)") (class "Default")
      (node (ref "IC7") (pin "10") (pinfunction "O_10") (pintype "output"))
      (node (ref "SV5") (pin "3") (pinfunction "3_3") (pintype "passive"))
    )
    (net (code "66") (name "Net-(IC7E-O)") (class "Default")
      (node (ref "IC7") (pin "12") (pinfunction "O_12") (pintype "output"))
      (node (ref "R23") (pin "2") (pinfunction "2_2") (pintype "passive"))
      (node (ref "SV5") (pin "5") (pinfunction "5_5") (pintype "passive"))
    )
    (net (code "67") (name "Net-(IC7F-I)") (class "Default")
      (node (ref "IC7") (pin "14") (pinfunction "I_14") (pintype "input"))
      (node (ref "R4") (pin "1") (pinfunction "1_1") (pintype "passive"))
    )
    (net (code "68") (name "Net-(IC7F-O)") (class "Default")
      (node (ref "IC7") (pin "15") (pinfunction "O_15") (pintype "output"))
      (node (ref "IC8") (pin "11") (pinfunction "CLK_11") (pintype "input"))
    )
    (net (code "69") (name "Net-(IC8A-D)") (class "Default")
      (node (ref "C30") (pin "2") (pinfunction "2_2") (pintype "passive"))
      (node (ref "IC8") (pin "2") (pinfunction "~{Q}_2") (pintype "output"))
      (node (ref "IC8") (pin "5") (pinfunction "D_5") (pintype "input"))
    )
    (net (code "70") (name "Net-(IC8B-D)") (class "Default")
      (node (ref "C28") (pin "2") (pinfunction "2_2") (pintype "passive"))
      (node (ref "IC8") (pin "12") (pinfunction "~{Q}_12") (pintype "output"))
      (node (ref "IC8") (pin "9") (pinfunction "D_9") (pintype "input"))
    )
    (net (code "71") (name "Net-(IC9A--IN)") (class "Default")
      (node (ref "IC9") (pin "1") (pinfunction "OUT_1") (pintype "output"))
      (node (ref "IC9") (pin "2") (pinfunction "-IN_2") (pintype "input"))
      (node (ref "R51") (pin "2") (pinfunction "2_2") (pintype "passive"))
    )
    (net (code "72") (name "Net-(IC9B-+IN)") (class "Default")
      (node (ref "IC9") (pin "5") (pinfunction "+IN_5") (pintype "input"))
      (node (ref "R51") (pin "1") (pinfunction "1_1") (pintype "passive"))
      (node (ref "R52") (pin "2") (pinfunction "2_2") (pintype "passive"))
    )
    (net (code "73") (name "Net-(IC9B-OUT)") (class "Default")
      (node (ref "IC9") (pin "7") (pinfunction "OUT_7") (pintype "output"))
      (node (ref "R52") (pin "1") (pinfunction "1_1") (pintype "passive"))
      (node (ref "R53") (pin "2") (pinfunction "2_2") (pintype "passive"))
    )
    (net (code "74") (name "Net-(IC9C-+IN)") (class "Default")
      (node (ref "IC9") (pin "10") (pinfunction "+IN_10") (pintype "input"))
      (node (ref "R2") (pin "1") (pinfunction "1_1") (pintype "passive"))
      (node (ref "R3") (pin "2") (pinfunction "2_2") (pintype "passive"))
    )
    (net (code "75") (name "Net-(IC9C-OUT)") (class "Default")
      (node (ref "IC9") (pin "8") (pinfunction "OUT_8") (pintype "output"))
      (node (ref "R3") (pin "1") (pinfunction "1_1") (pintype "passive"))
      (node (ref "R4") (pin "2") (pinfunction "2_2") (pintype "passive"))
    )
    (net (code "76") (name "Net-(IC9D--IN)") (class "Default")
      (node (ref "IC9") (pin "13") (pinfunction "-IN_13") (pintype "input"))
      (node (ref "IC9") (pin "14") (pinfunction "OUT_14") (pintype "output"))
      (node (ref "R2") (pin "2") (pinfunction "2_2") (pintype "passive"))
    )
    (net (code "77") (name "Net-(IC10A-+IN)") (class "Default")
      (node (ref "IC10") (pin "3") (pinfunction "+IN_3") (pintype "input"))
      (node (ref "R57") (pin "1") (pinfunction "1_1") (pintype "passive"))
      (node (ref "R58") (pin "1") (pinfunction "1_1") (pintype "passive"))
    )
    (net (code "78") (name "Net-(IC10A--IN)") (class "Default")
      (node (ref "IC10") (pin "1") (pinfunction "OUT_1") (pintype "output"))
      (node (ref "IC10") (pin "2") (pinfunction "-IN_2") (pintype "input"))
      (node (ref "R59") (pin "2") (pinfunction "2_2") (pintype "passive"))
    )
    (net (code "79") (name "Net-(IC10B--IN)") (class "Default")
      (node (ref "IC10") (pin "6") (pinfunction "-IN_6") (pintype "input"))
      (node (ref "R63") (pin "1") (pinfunction "A_1") (pintype "passive"))
      (node (ref "R64") (pin "1") (pinfunction "1_1") (pintype "passive"))
    )
    (net (code "80") (name "Net-(IC10B-OUT)") (class "Default")
      (node (ref "IC10") (pin "7") (pinfunction "OUT_7") (pintype "output"))
      (node (ref "R60") (pin "2") (pinfunction "2_2") (pintype "passive"))
      (node (ref "R63") (pin "2") (pinfunction "S_2") (pintype "passive"))
    )
    (net (code "81") (name "Net-(IC10C--IN)") (class "Default")
      (node (ref "IC10") (pin "9") (pinfunction "-IN_9") (pintype "input"))
      (node (ref "R1") (pin "1") (pinfunction "A_1") (pintype "passive"))
      (node (ref "R48") (pin "1") (pinfunction "1_1") (pintype "passive"))
    )
    (net (code "82") (name "Net-(IC10C-OUT)") (class "Default")
      (node (ref "IC10") (pin "8") (pinfunction "OUT_8") (pintype "output"))
      (node (ref "R1") (pin "2") (pinfunction "S_2") (pintype "passive"))
      (node (ref "R47") (pin "2") (pinfunction "2_2") (pintype "passive"))
    )
    (net (code "83") (name "Net-(IC10D-+IN)") (class "Default")
      (node (ref "IC10") (pin "12") (pinfunction "+IN_12") (pintype "input"))
      (node (ref "R23") (pin "1") (pinfunction "1_1") (pintype "passive"))
      (node (ref "R24") (pin "1") (pinfunction "1_1") (pintype "passive"))
    )
    (net (code "84") (name "Net-(IC10D--IN)") (class "Default")
      (node (ref "IC10") (pin "13") (pinfunction "-IN_13") (pintype "input"))
      (node (ref "IC10") (pin "14") (pinfunction "OUT_14") (pintype "output"))
      (node (ref "R44") (pin "2") (pinfunction "2_2") (pintype "passive"))
    )
    (net (code "85") (name "Net-(IC11A--IN)") (class "Default")
      (node (ref "IC11") (pin "2") (pinfunction "-IN_2") (pintype "input"))
      (node (ref "R59") (pin "1") (pinfunction "1_1") (pintype "passive"))
      (node (ref "R60") (pin "1") (pinfunction "1_1") (pintype "passive"))
      (node (ref "R61") (pin "2") (pinfunction "2_2") (pintype "passive"))
    )
    (net (code "86") (name "Net-(IC11A-OUT)") (class "Default")
      (node (ref "C22") (pin "+") (pinfunction "+_+") (pintype "passive"))
      (node (ref "IC11") (pin "1") (pinfunction "OUT_1") (pintype "output"))
      (node (ref "R61") (pin "1") (pinfunction "1_1") (pintype "passive"))
    )
    (net (code "87") (name "Net-(IC11B-+IN)") (class "Default")
      (node (ref "IC11") (pin "5") (pinfunction "+IN_5") (pintype "input"))
      (node (ref "R54") (pin "2") (pinfunction "2_2") (pintype "passive"))
      (node (ref "R55") (pin "2") (pinfunction "2_2") (pintype "passive"))
    )
    (net (code "88") (name "Net-(IC11B--IN)") (class "Default")
      (node (ref "C21") (pin "+") (pinfunction "+_+") (pintype "passive"))
      (node (ref "IC11") (pin "6") (pinfunction "-IN_6") (pintype "input"))
      (node (ref "IC11") (pin "7") (pinfunction "OUT_7") (pintype "output"))
    )
    (net (code "89") (name "Net-(IC11C-+IN)") (class "Default")
      (node (ref "IC11") (pin "10") (pinfunction "+IN_10") (pintype "input"))
      (node (ref "R25") (pin "2") (pinfunction "2_2") (pintype "passive"))
      (node (ref "R26") (pin "2") (pinfunction "2_2") (pintype "passive"))
    )
    (net (code "90") (name "Net-(IC11C--IN)") (class "Default")
      (node (ref "C13") (pin "+") (pinfunction "+_+") (pintype "passive"))
      (node (ref "IC11") (pin "8") (pinfunction "OUT_8") (pintype "output"))
      (node (ref "IC11") (pin "9") (pinfunction "-IN_9") (pintype "input"))
    )
    (net (code "91") (name "Net-(IC11D--IN)") (class "Default")
      (node (ref "IC11") (pin "13") (pinfunction "-IN_13") (pintype "input"))
      (node (ref "R44") (pin "1") (pinfunction "1_1") (pintype "passive"))
      (node (ref "R45") (pin "2") (pinfunction "2_2") (pintype "passive"))
      (node (ref "R47") (pin "1") (pinfunction "1_1") (pintype "passive"))
    )
    (net (code "92") (name "Net-(IC11D-OUT)") (class "Default")
      (node (ref "C14") (pin "+") (pinfunction "+_+") (pintype "passive"))
      (node (ref "IC11") (pin "14") (pinfunction "OUT_14") (pintype "output"))
      (node (ref "R45") (pin "1") (pinfunction "1_1") (pintype "passive"))
    )
    (net (code "93") (name "Net-(IC12A-CLK)") (class "Default")
      (node (ref "IC12") (pin "3") (pinfunction "CLK_3") (pintype "input"))
      (node (ref "IC7") (pin "7") (pinfunction "I_7") (pintype "input"))
      (node (ref "IC8") (pin "1") (pinfunction "Q_1") (pintype "output"))
    )
    (net (code "94") (name "Net-(IC12A-D)") (class "Default")
      (node (ref "C29") (pin "2") (pinfunction "2_2") (pintype "passive"))
      (node (ref "IC12") (pin "2") (pinfunction "~{Q}_2") (pintype "output"))
      (node (ref "IC12") (pin "5") (pinfunction "D_5") (pintype "input"))
    )
    (net (code "95") (name "Net-(IC12A-Q)") (class "Default")
      (node (ref "IC12") (pin "1") (pinfunction "Q_1") (pintype "output"))
      (node (ref "IC7") (pin "5") (pinfunction "I_5") (pintype "input"))
    )
    (net (code "96") (name "Net-(IC12B-CLK)") (class "Default")
      (node (ref "IC12") (pin "11") (pinfunction "CLK_11") (pintype "input"))
      (node (ref "IC7") (pin "11") (pinfunction "I_11") (pintype "input"))
      (node (ref "IC8") (pin "13") (pinfunction "Q_13") (pintype "output"))
    )
    (net (code "97") (name "Net-(IC12B-D)") (class "Default")
      (node (ref "C27") (pin "2") (pinfunction "2_2") (pintype "passive"))
      (node (ref "IC12") (pin "12") (pinfunction "~{Q}_12") (pintype "output"))
      (node (ref "IC12") (pin "9") (pinfunction "D_9") (pintype "input"))
    )
    (net (code "98") (name "Net-(IC12B-Q)") (class "Default")
      (node (ref "IC12") (pin "13") (pinfunction "Q_13") (pintype "output"))
      (node (ref "IC7") (pin "9") (pinfunction "I_9") (pintype "input"))
    )
    (net (code "99") (name "Net-(POWERB-S)") (class "Default")
      (node (ref "JP2") (pin "2") (pinfunction "2_2") (pintype "passive"))
      (node (ref "POWER") (pin "2") (pinfunction "S_2") (pintype "passive"))
      (node (ref "R16") (pin "1") (pinfunction "1_1") (pintype "passive"))
    )
    (net (code "100") (name "Net-(POWERF-S)") (class "Default")
      (node (ref "JP1") (pin "1") (pinfunction "1_1") (pintype "passive"))
      (node (ref "POWER") (pin "6") (pinfunction "S_6") (pintype "passive"))
      (node (ref "R15") (pin "1") (pinfunction "1_1") (pintype "passive"))
    )
    (net (code "101") (name "Net-(R10-Pad1)") (class "Default")
      (node (ref "R10") (pin "1") (pinfunction "1_1") (pintype "passive"))
      (node (ref "SV1") (pin "7") (pinfunction "7_7") (pintype "passive"))
    )
    (net (code "102") (name "Net-(R12-Pad2)") (class "Default")
      (node (ref "R12") (pin "2") (pinfunction "2_2") (pintype "passive"))
      (node (ref "R8") (pin "1") (pinfunction "1_1") (pintype "passive"))
      (node (ref "R9") (pin "1") (pinfunction "1_1") (pintype "passive"))
    )
    (net (code "103") (name "Net-(R25-Pad1)") (class "Default")
      (node (ref "R25") (pin "1") (pinfunction "1_1") (pintype "passive"))
      (node (ref "SV5") (pin "7") (pinfunction "7_7") (pintype "passive"))
    )
    (net (code "104") (name "Net-(R30-Pad1)") (class "Default")
      (node (ref "R30") (pin "1") (pinfunction "1_1") (pintype "passive"))
      (node (ref "SV2") (pin "3") (pinfunction "3_3") (pintype "passive"))
    )
    (net (code "105") (name "Net-(R40-Pad2)") (class "Default")
      (node (ref "R40") (pin "2") (pinfunction "2_2") (pintype "passive"))
      (node (ref "R41") (pin "1") (pinfunction "1_1") (pintype "passive"))
      (node (ref "R42") (pin "1") (pinfunction "1_1") (pintype "passive"))
    )
    (net (code "106") (name "Net-(R48-Pad2)") (class "Default")
      (node (ref "R48") (pin "2") (pinfunction "2_2") (pintype "passive"))
      (node (ref "R49") (pin "1") (pinfunction "1_1") (pintype "passive"))
      (node (ref "R50") (pin "1") (pinfunction "1_1") (pintype "passive"))
    )
    (net (code "107") (name "Net-(R54-Pad1)") (class "Default")
      (node (ref "R54") (pin "1") (pinfunction "1_1") (pintype "passive"))
      (node (ref "SV6") (pin "3") (pinfunction "3_3") (pintype "passive"))
    )
    (net (code "108") (name "Net-(R64-Pad2)") (class "Default")
      (node (ref "R64") (pin "2") (pinfunction "2_2") (pintype "passive"))
      (node (ref "R65") (pin "1") (pinfunction "1_1") (pintype "passive"))
      (node (ref "R66") (pin "1") (pinfunction "1_1") (pintype "passive"))
    )
    (net (code "109") (name "Net-(SV1-Pad1)") (class "Default")
      (node (ref "SV1") (pin "1") (pinfunction "1_1") (pintype "passive"))
      (node (ref "SV1") (pin "6") (pinfunction "6_6") (pintype "passive"))
    )
    (net (code "110") (name "Net-(SV1-Pad2)") (class "Default")
      (node (ref "SV1") (pin "2") (pinfunction "2_2") (pintype "passive"))
      (node (ref "SV1") (pin "4") (pinfunction "4_4") (pintype "passive"))
    )
    (net (code "111") (name "Net-(SV1-Pad10)") (class "Default")
      (node (ref "SV1") (pin "10") (pinfunction "10_10") (pintype "passive"))
      (node (ref "SV1") (pin "8") (pinfunction "8_8") (pintype "passive"))
    )
    (net (code "112") (name "Net-(SV2-Pad2)") (class "Default")
      (node (ref "SV2") (pin "2") (pinfunction "2_2") (pintype "passive"))
      (node (ref "SV2") (pin "4") (pinfunction "4_4") (pintype "passive"))
    )
    (net (code "113") (name "Net-(SV2-Pad6)") (class "Default")
      (node (ref "SV2") (pin "6") (pinfunction "6_6") (pintype "passive"))
      (node (ref "SV2") (pin "9") (pinfunction "9_9") (pintype "passive"))
    )
    (net (code "114") (name "Net-(SV2-Pad10)") (class "Default")
      (node (ref "SV2") (pin "10") (pinfunction "10_10") (pintype "passive"))
      (node (ref "SV2") (pin "8") (pinfunction "8_8") (pintype "passive"))
    )
    (net (code "115") (name "Net-(SV3-Pad2)") (class "Default")
      (node (ref "SV3") (pin "2") (pinfunction "2_2") (pintype "passive"))
      (node (ref "SV3") (pin "3") (pinfunction "3_3") (pintype "passive"))
    )
    (net (code "116") (name "Net-(SV3-Pad5)") (class "Default")
      (node (ref "SV3") (pin "5") (pinfunction "5_5") (pintype "passive"))
      (node (ref "SV3") (pin "6") (pinfunction "6_6") (pintype "passive"))
    )
    (net (code "117") (name "Net-(SV3-Pad8)") (class "Default")
      (node (ref "SV3") (pin "8") (pinfunction "8_8") (pintype "passive"))
      (node (ref "SV3") (pin "9") (pinfunction "9_9") (pintype "passive"))
    )
    (net (code "118") (name "Net-(SV3-Pad11)") (class "Default")
      (node (ref "SV3") (pin "11") (pinfunction "11_11") (pintype "passive"))
      (node (ref "SV3") (pin "12") (pinfunction "12_12") (pintype "passive"))
    )
    (net (code "119") (name "Net-(SV3-Pad14)") (class "Default")
      (node (ref "SV3") (pin "14") (pinfunction "14_14") (pintype "passive"))
      (node (ref "SV3") (pin "15") (pinfunction "15_15") (pintype "passive"))
    )
    (net (code "120") (name "Net-(SV4-Pad2)") (class "Default")
      (node (ref "SV4") (pin "2") (pinfunction "2_2") (pintype "passive"))
      (node (ref "SV4") (pin "3") (pinfunction "3_3") (pintype "passive"))
    )
    (net (code "121") (name "Net-(SV4-Pad5)") (class "Default")
      (node (ref "SV4") (pin "5") (pinfunction "5_5") (pintype "passive"))
      (node (ref "SV4") (pin "6") (pinfunction "6_6") (pintype "passive"))
    )
    (net (code "122") (name "Net-(SV4-Pad8)") (class "Default")
      (node (ref "SV4") (pin "8") (pinfunction "8_8") (pintype "passive"))
      (node (ref "SV4") (pin "9") (pinfunction "9_9") (pintype "passive"))
    )
    (net (code "123") (name "Net-(SV4-Pad11)") (class "Default")
      (node (ref "SV4") (pin "11") (pinfunction "11_11") (pintype "passive"))
      (node (ref "SV4") (pin "12") (pinfunction "12_12") (pintype "passive"))
    )
    (net (code "124") (name "Net-(SV5-Pad1)") (class "Default")
      (node (ref "SV5") (pin "1") (pinfunction "1_1") (pintype "passive"))
      (node (ref "SV5") (pin "6") (pinfunction "6_6") (pintype "passive"))
    )
    (net (code "125") (name "Net-(SV5-Pad2)") (class "Default")
      (node (ref "SV5") (pin "2") (pinfunction "2_2") (pintype "passive"))
      (node (ref "SV5") (pin "4") (pinfunction "4_4") (pintype "passive"))
    )
    (net (code "126") (name "Net-(SV5-Pad10)") (class "Default")
      (node (ref "SV5") (pin "10") (pinfunction "10_10") (pintype "passive"))
      (node (ref "SV5") (pin "8") (pinfunction "8_8") (pintype "passive"))
    )
    (net (code "127") (name "Net-(SV6-Pad2)") (class "Default")
      (node (ref "SV6") (pin "2") (pinfunction "2_2") (pintype "passive"))
      (node (ref "SV6") (pin "4") (pinfunction "4_4") (pintype "passive"))
    )
    (net (code "128") (name "Net-(SV6-Pad6)") (class "Default")
      (node (ref "SV6") (pin "6") (pinfunction "6_6") (pintype "passive"))
      (node (ref "SV6") (pin "9") (pinfunction "9_9") (pintype "passive"))
    )
    (net (code "129") (name "Net-(SV6-Pad10)") (class "Default")
      (node (ref "SV6") (pin "10") (pinfunction "10_10") (pintype "passive"))
      (node (ref "SV6") (pin "8") (pinfunction "8_8") (pintype "passive"))
    )
    (net (code "130") (name "Net-(SV7-Pad2)") (class "Default")
      (node (ref "SV7") (pin "2") (pinfunction "2_2") (pintype "passive"))
      (node (ref "SV7") (pin "3") (pinfunction "3_3") (pintype "passive"))
    )
    (net (code "131") (name "Net-(SV7-Pad5)") (class "Default")
      (node (ref "SV7") (pin "5") (pinfunction "5_5") (pintype "passive"))
      (node (ref "SV7") (pin "6") (pinfunction "6_6") (pintype "passive"))
    )
    (net (code "132") (name "Net-(SV7-Pad8)") (class "Default")
      (node (ref "SV7") (pin "8") (pinfunction "8_8") (pintype "passive"))
      (node (ref "SV7") (pin "9") (pinfunction "9_9") (pintype "passive"))
    )
    (net (code "133") (name "Net-(SV7-Pad11)") (class "Default")
      (node (ref "SV7") (pin "11") (pinfunction "11_11") (pintype "passive"))
      (node (ref "SV7") (pin "12") (pinfunction "12_12") (pintype "passive"))
    )
    (net (code "134") (name "V+") (class "Default")
      (node (ref "C1") (pin "1") (pinfunction "1_1") (pintype "passive"))
      (node (ref "C10") (pin "1") (pinfunction "1_1") (pintype "passive"))
      (node (ref "C15") (pin "1") (pinfunction "1_1") (pintype "passive"))
      (node (ref "C16") (pin "1") (pinfunction "1_1") (pintype "passive"))
      (node (ref "C17") (pin "1") (pinfunction "1_1") (pintype "passive"))
      (node (ref "C18") (pin "1") (pinfunction "1_1") (pintype "passive"))
      (node (ref "C19") (pin "1") (pinfunction "1_1") (pintype "passive"))
      (node (ref "C2") (pin "1") (pinfunction "1_1") (pintype "passive"))
      (node (ref "C20") (pin "1") (pinfunction "1_1") (pintype "passive"))
      (node (ref "C3") (pin "1") (pinfunction "1_1") (pintype "passive"))
      (node (ref "C4") (pin "1") (pinfunction "1_1") (pintype "passive"))
      (node (ref "C5") (pin "+") (pinfunction "+_+") (pintype "passive"))
      (node (ref "C9") (pin "1") (pinfunction "1_1") (pintype "passive"))
      (node (ref "IC1") (pin "14") (pinfunction "VDD_14") (pintype "power_in"))
      (node (ref "IC12") (pin "14") (pinfunction "VDD_14") (pintype "power_in"))
      (node (ref "IC3") (pin "1") (pinfunction "VDD_1") (pintype "power_in"))
      (node (ref "IC6") (pin "14") (pinfunction "VDD_14") (pintype "power_in"))
      (node (ref "IC7") (pin "1") (pinfunction "VDD_1") (pintype "power_in"))
      (node (ref "IC8") (pin "14") (pinfunction "VDD_14") (pintype "power_in"))
      (node (ref "JP3") (pin "1") (pinfunction "1_1") (pintype "passive"))
      (node (ref "R15") (pin "2") (pinfunction "2_2") (pintype "passive"))
    )
    (net (code "135") (name "V-") (class "Default")
      (node (ref "C10") (pin "2") (pinfunction "2_2") (pintype "passive"))
      (node (ref "C15") (pin "2") (pinfunction "2_2") (pintype "passive"))
      (node (ref "C18") (pin "2") (pinfunction "2_2") (pintype "passive"))
      (node (ref "C20") (pin "2") (pinfunction "2_2") (pintype "passive"))
      (node (ref "C3") (pin "2") (pinfunction "2_2") (pintype "passive"))
      (node (ref "C4") (pin "2") (pinfunction "2_2") (pintype "passive"))
      (node (ref "C6") (pin "-") (pinfunction "-_-") (pintype "passive"))
      (node (ref "JP4") (pin "2") (pinfunction "2_2") (pintype "passive"))
      (node (ref "R16") (pin "2") (pinfunction "2_2") (pintype "passive"))
    )
    (net (code "136") (name "unconnected-(POWERD-S-Pad4)") (class "Default")
      (node (ref "POWER") (pin "4") (pinfunction "S_4") (pintype "passive"))
    )
    (net (code "137") (name "unconnected-(POWERE-S-Pad5)") (class "Default")
      (node (ref "POWER") (pin "5") (pinfunction "S_5") (pintype "passive"))
    )
    (net (code "138") (name "unconnected-(R1-E-Pad3)") (class "Default")
      (node (ref "R1") (pin "3") (pinfunction "E_3") (pintype "passive"))
    )
    (net (code "139") (name "unconnected-(R17-E-Pad3)") (class "Default")
      (node (ref "R17") (pin "3") (pinfunction "E_3") (pintype "passive"))
    )
    (net (code "140") (name "unconnected-(R39-E-Pad3)") (class "Default")
      (node (ref "R39") (pin "3") (pinfunction "E_3") (pintype "passive"))
    )
    (net (code "141") (name "unconnected-(R63-E-Pad3)") (class "Default")
      (node (ref "R63") (pin "3") (pinfunction "E_3") (pintype "passive"))
    )
    (net (code "142") (name "unconnected-(SV1-Pad9)") (class "Default")
      (node (ref "SV1") (pin "9") (pinfunction "9_9") (pintype "passive"))
    )
    (net (code "143") (name "unconnected-(SV2-Pad1)") (class "Default")
      (node (ref "SV2") (pin "1") (pinfunction "1_1") (pintype "passive"))
    )
    (net (code "144") (name "unconnected-(SV5-Pad9)") (class "Default")
      (node (ref "SV5") (pin "9") (pinfunction "9_9") (pintype "passive"))
    )
    (net (code "145") (name "unconnected-(SV6-Pad1)") (class "Default")
      (node (ref "SV6") (pin "1") (pinfunction "1_1") (pintype "passive"))
    )
  )
)
